# gaius.net
KiCad netlist of a schematic drawn in EAGLE
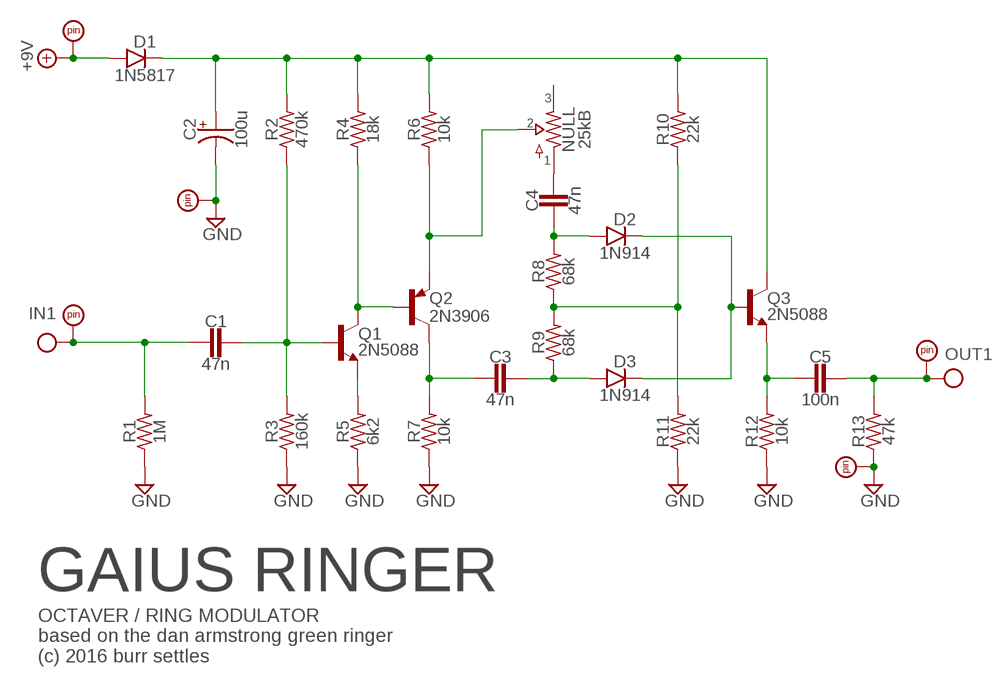
[diagram p0: schematic, sheet 1]

(export (version "E")
  (design (tool "Eeschema 10.0.6"))
  (components
    (comp (ref "C1")
      (value "47n")
      (footprint "eagle-import:BOX_SMALL")
      (libsource (lib "eagle-import") (part "CER/FILMBOX.1"))
    )
    (comp (ref "C2")
      (value "100u")
      (footprint "eagle-import:050_020_1")
      (libsource (lib "eagle-import") (part "0501"))
    )
    (comp (ref "C3")
      (value "47n")
      (footprint "eagle-import:BOX_SMALL")
      (libsource (lib "eagle-import") (part "CER/FILMBOX.1"))
    )
    (comp (ref "C4")
      (value "47n")
      (footprint "eagle-import:BOX_SMALL")
      (libsource (lib "eagle-import") (part "CER/FILMBOX.1"))
    )
    (comp (ref "C5")
      (value "100n")
      (footprint "eagle-import:BOX_SMALL")
      (libsource (lib "eagle-import") (part "CER/FILMBOX.1"))
    )
    (comp (ref "D1")
      (value "1N5817")
      (footprint "eagle-import:DO41-2")
      (libsource (lib "eagle-import") (part "DO41.2"))
    )
    (comp (ref "D2")
      (value "1N914")
      (footprint "eagle-import:DO35-2")
      (libsource (lib "eagle-import") (part "DO35.2"))
    )
    (comp (ref "D3")
      (value "1N914")
      (footprint "eagle-import:DO35-2")
      (libsource (lib "eagle-import") (part "DO35.2"))
    )
    (comp (ref "NULL")
      (value "25kB")
      (footprint "eagle-import:2262_TRIM")
      (libsource (lib "eagle-import") (part "POTSTRIM"))
    )
    (comp (ref "PAD1")
      (value "PADSQR")
      (footprint "eagle-import:SQUARE")
      (libsource (lib "eagle-import") (part "PADSQR"))
    )
    (comp (ref "PAD2")
      (value "PADSQR")
      (footprint "eagle-import:SQUARE")
      (libsource (lib "eagle-import") (part "PADSQR"))
    )
    (comp (ref "PAD3")
      (value "PADRND")
      (footprint "eagle-import:ROUND")
      (libsource (lib "eagle-import") (part "PADRND"))
    )
    (comp (ref "PAD4")
      (value "PADRND")
      (footprint "eagle-import:ROUND")
      (libsource (lib "eagle-import") (part "PADRND"))
    )
    (comp (ref "PAD5")
      (value "PADSQR")
      (footprint "eagle-import:SQUARE")
      (libsource (lib "eagle-import") (part "PADSQR"))
    )
    (comp (ref "Q1")
      (value "2N5088")
      (footprint "eagle-import:TO92-")
      (libsource (lib "eagle-import") (part "2N5088"))
    )
    (comp (ref "Q2")
      (value "2N3906")
      (footprint "eagle-import:TO92-")
      (libsource (lib "eagle-import") (part "2N3906-"))
    )
    (comp (ref "Q3")
      (value "2N5088")
      (footprint "eagle-import:TO92-")
      (libsource (lib "eagle-import") (part "2N5088"))
    )
    (comp (ref "R1")
      (value "1M")
      (footprint "eagle-import:R0207_3")
      (libsource (lib "eagle-import") (part "R_.3B"))
    )
    (comp (ref "R2")
      (value "470k")
      (footprint "eagle-import:R0207_3")
      (libsource (lib "eagle-import") (part "R_.3B"))
    )
    (comp (ref "R3")
      (value "160k")
      (footprint "eagle-import:R0207_3")
      (libsource (lib "eagle-import") (part "R_.3B"))
    )
    (comp (ref "R4")
      (value "18k")
      (footprint "eagle-import:R0207_3")
      (libsource (lib "eagle-import") (part "R_.3B"))
    )
    (comp (ref "R5")
      (value "6k2")
      (footprint "eagle-import:R0207_3")
      (libsource (lib "eagle-import") (part "R_.3B"))
    )
    (comp (ref "R6")
      (value "10k")
      (footprint "eagle-import:R0207_3")
      (libsource (lib "eagle-import") (part "R_.3B"))
    )
    (comp (ref "R7")
      (value "10k")
      (footprint "eagle-import:R0207_3")
      (libsource (lib "eagle-import") (part "R_.3B"))
    )
    (comp (ref "R8")
      (value "68k")
      (footprint "eagle-import:R0207_3")
      (libsource (lib "eagle-import") (part "R_.3B"))
    )
    (comp (ref "R9")
      (value "68k")
      (footprint "eagle-import:R0207_3")
      (libsource (lib "eagle-import") (part "R_.3B"))
    )
    (comp (ref "R10")
      (value "22k")
      (footprint "eagle-import:R0207_3")
      (libsource (lib "eagle-import") (part "R_.3B"))
    )
    (comp (ref "R11")
      (value "22k")
      (footprint "eagle-import:R0207_3")
      (libsource (lib "eagle-import") (part "R_.3B"))
    )
    (comp (ref "R12")
      (value "10k")
      (footprint "eagle-import:R0207_3")
      (libsource (lib "eagle-import") (part "R_.3B"))
    )
    (comp (ref "R13")
      (value "47k")
      (footprint "eagle-import:R0207_3")
      (libsource (lib "eagle-import") (part "R_.3B"))
    )
  )
  (nets
    (net (code "1") (name "+9V") (class "Default")
      (node (ref "D1") (pin "A") (pinfunction "A_A") (pintype "passive"))
      (node (ref "PAD1") (pin "1") (pinfunction "P$1_1") (pintype "bidirectional"))
    )
    (net (code "2") (name "GND") (class "Default")
      (node (ref "C2") (pin "-") (pinfunction "-_-") (pintype "passive"))
      (node (ref "PAD3") (pin "1") (pinfunction "P$1_1") (pintype "bidirectional"))
      (node (ref "PAD4") (pin "1") (pinfunction "P$1_1") (pintype "bidirectional"))
      (node (ref "R1") (pin "1") (pinfunction "1_1") (pintype "passive"))
      (node (ref "R11") (pin "1") (pinfunction "1_1") (pintype "passive"))
      (node (ref "R12") (pin "1") (pinfunction "1_1") (pintype "passive"))
      (node (ref "R13") (pin "1") (pinfunction "1_1") (pintype "passive"))
      (node (ref "R3") (pin "1") (pinfunction "1_1") (pintype "passive"))
      (node (ref "R5") (pin "1") (pinfunction "1_1") (pintype "passive"))
      (node (ref "R7") (pin "1") (pinfunction "1_1") (pintype "passive"))
    )
    (net (code "3") (name "IN") (class "Default")
      (node (ref "C1") (pin "2") (pinfunction "2_2") (pintype "passive"))
      (node (ref "PAD2") (pin "1") (pinfunction "P$1_1") (pintype "bidirectional"))
      (node (ref "R1") (pin "2") (pinfunction "2_2") (pintype "passive"))
    )
    (net (code "4") (name "Net-(C3-Pad1)") (class "Default")
      (node (ref "C3") (pin "1") (pinfunction "1_1") (pintype "passive"))
      (node (ref "D3") (pin "A") (pinfunction "A_A") (pintype "passive"))
      (node (ref "R9") (pin "1") (pinfunction "1_1") (pintype "passive"))
    )
    (net (code "5") (name "Net-(C4-Pad1)") (class "Default")
      (node (ref "C4") (pin "1") (pinfunction "1_1") (pintype "passive"))
      (node (ref "NULL") (pin "1") (pinfunction "1_1") (pintype "passive"))
    )
    (net (code "6") (name "Net-(C4-Pad2)") (class "Default")
      (node (ref "C4") (pin "2") (pinfunction "2_2") (pintype "passive"))
      (node (ref "D2") (pin "A") (pinfunction "A_A") (pintype "passive"))
      (node (ref "R8") (pin "2") (pinfunction "2_2") (pintype "passive"))
    )
    (net (code "7") (name "Net-(Q1-B)") (class "Default")
      (node (ref "C1") (pin "1") (pinfunction "1_1") (pintype "passive"))
      (node (ref "Q1") (pin "2") (pinfunction "B_2") (pintype "passive"))
      (node (ref "R2") (pin "1") (pinfunction "1_1") (pintype "passive"))
      (node (ref "R3") (pin "2") (pinfunction "2_2") (pintype "passive"))
    )
    (net (code "8") (name "Net-(Q1-C)") (class "Default")
      (node (ref "Q1") (pin "1") (pinfunction "C_1") (pintype "passive"))
      (node (ref "Q2") (pin "2") (pinfunction "B_2") (pintype "passive"))
      (node (ref "R4") (pin "1") (pinfunction "1_1") (pintype "passive"))
    )
    (net (code "9") (name "Net-(Q1-E)") (class "Default")
      (node (ref "Q1") (pin "3") (pinfunction "E_3") (pintype "passive"))
      (node (ref "R5") (pin "2") (pinfunction "2_2") (pintype "passive"))
    )
    (net (code "10") (name "Net-(Q2-C)") (class "Default")
      (node (ref "C3") (pin "2") (pinfunction "2_2") (pintype "passive"))
      (node (ref "Q2") (pin "1") (pinfunction "C_1") (pintype "passive"))
      (node (ref "R7") (pin "2") (pinfunction "2_2") (pintype "passive"))
    )
    (net (code "11") (name "Net-(Q2-E)") (class "Default")
      (node (ref "NULL") (pin "2") (pinfunction "2_2") (pintype "passive"))
      (node (ref "Q2") (pin "3") (pinfunction "E_3") (pintype "passive"))
      (node (ref "R6") (pin "1") (pinfunction "1_1") (pintype "passive"))
    )
    (net (code "12") (name "Net-(Q3-B)") (class "Default")
      (node (ref "D2") (pin "C") (pinfunction "C_C") (pintype "passive"))
      (node (ref "D3") (pin "C") (pinfunction "C_C") (pintype "passive"))
      (node (ref "Q3") (pin "2") (pinfunction "B_2") (pintype "passive"))
    )
    (net (code "13") (name "Net-(Q3-C)") (class "Default")
      (node (ref "C2") (pin "+") (pinfunction "+_+") (pintype "passive"))
      (node (ref "D1") (pin "C") (pinfunction "C_C") (pintype "passive"))
      (node (ref "Q3") (pin "1") (pinfunction "C_1") (pintype "passive"))
      (node (ref "R10") (pin "2") (pinfunction "2_2") (pintype "passive"))
      (node (ref "R2") (pin "2") (pinfunction "2_2") (pintype "passive"))
      (node (ref "R4") (pin "2") (pinfunction "2_2") (pintype "passive"))
      (node (ref "R6") (pin "2") (pinfunction "2_2") (pintype "passive"))
    )
    (net (code "14") (name "Net-(Q3-E)") (class "Default")
      (node (ref "C5") (pin "2") (pinfunction "2_2") (pintype "passive"))
      (node (ref "Q3") (pin "3") (pinfunction "E_3") (pintype "passive"))
      (node (ref "R12") (pin "2") (pinfunction "2_2") (pintype "passive"))
    )
    (net (code "15") (name "Net-(R10-Pad1)") (class "Default")
      (node (ref "R10") (pin "1") (pinfunction "1_1") (pintype "passive"))
      (node (ref "R11") (pin "2") (pinfunction "2_2") (pintype "passive"))
      (node (ref "R8") (pin "1") (pinfunction "1_1") (pintype "passive"))
      (node (ref "R9") (pin "2") (pinfunction "2_2") (pintype "passive"))
    )
    (net (code "16") (name "OUT") (class "Default")
      (node (ref "C5") (pin "1") (pinfunction "1_1") (pintype "passive"))
      (node (ref "PAD5") (pin "1") (pinfunction "P$1_1") (pintype "bidirectional"))
      (node (ref "R13") (pin "2") (pinfunction "2_2") (pintype "passive"))
    )
    (net (code "17") (name "unconnected-(NULL-Pad3)") (class "Default")
      (node (ref "NULL") (pin "3") (pinfunction "3_3") (pintype "passive"))
    )
  )
)
